# Sheet1.net
KiCad netlist of a schematic drawn in Altium Designer
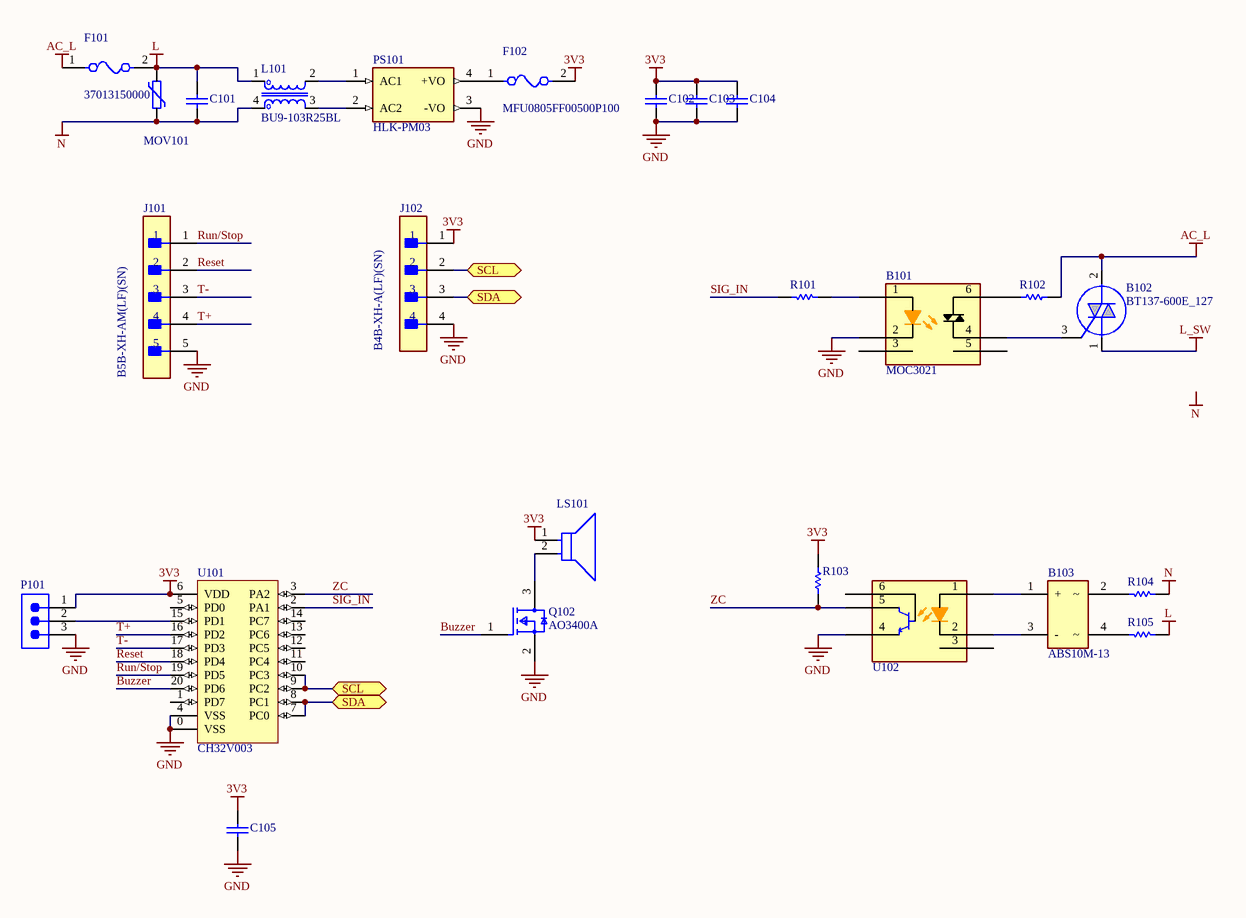
[diagram p0: Sheet1.SchDoc]

(export (version "E")
  (design (tool "Eeschema 10.0.6"))
  (components
    (comp (ref "B101")
      (value "MOC3021")
      (footprint "MOC3021")
      (fields (field (name "MOUSER PART NUMBER") "859-MOC3021"))
      (libsource (lib "Schlib1") (part "MOC3021"))
    )
    (comp (ref "B102")
      (value "BT137-600E_127")
      (footprint "TO254P470X1000X2000-3P")
      (fields
        (field (name "MANUFACTURER_PART_NUMBER") "BT137-600E,127")
        (field (name "MOUSER PART NUMBER") "771-BT137-600E")
      )
      (libsource (lib "Schlib1") (part "BT137-600E_127"))
    )
    (comp (ref "B103")
      (value "ABS10M-13")
      (footprint "SOP400P660X140-4N")
      (description "Bridge Rectifier Single Phase Standard 1 kV Surface Mount 4-SOPA (Type WX)")
      (fields (field (name "MOUSER PART NUMBER") "621-ABS10M-13"))
      (libsource (lib "Schlib1") (part "ABS10M-13"))
    )
    (comp (ref "C101")
      (value "890324023023")
      (footprint "WCAP-FTX2_L13W7H13")
      (fields (field (name "TOLERANCE") "10%"))
      (libsource (lib "Altium Content Vault") (part "Capacitor_Non-Polarized"))
    )
    (comp (ref "C102")
      (value "Capacitor")
      (footprint "CAPC2013X13N")
      (libsource (lib "Schlib1") (part "C0805"))
    )
    (comp (ref "C103")
      (value "Capacitor")
      (footprint "CAPC2013X13N")
      (libsource (lib "Schlib1") (part "C0805"))
    )
    (comp (ref "C104")
      (value "Capacitor")
      (footprint "CAPC2013X13N")
      (libsource (lib "Schlib1") (part "C0805"))
    )
    (comp (ref "C105")
      (value "Capacitor")
      (footprint "CAPC1608X09N")
      (libsource (lib "Schlib1") (part "C0603"))
    )
    (comp (ref "F101")
      (value "37013150000")
      (footprint "FP-370-MFG")
      (description "FUSE BRD MNT 3.15A 250VAC RADIAL")
      (libsource (lib "Altium Content Vault") (part "5bcf9b9f640e542cf0359d10258e979"))
    )
    (comp (ref "F102")
      (value "MFU0805FF00500P100")
      (footprint "FP-MFU0805-MFG")
      (libsource (lib "Altium Content Vault") (part "5bcf9b9f640e542cf0359d10258e979"))
    )
    (comp (ref "J101")
      (value "B5B-XH-AM(LF)(SN)")
      (footprint "FP-B5B-XH-AM_LF_SN-MFG")
      (description "CONN HEADER VERT 5POS 2.5MM")
      (libsource (lib "Altium Content Vault") (part "bf93c07fd2649a848d0ec8585582aab"))
    )
    (comp (ref "J102")
      (value "B4B-XH-A(LF)(SN)")
      (footprint "FP-B4B-XH-A_LF_SN-MFG")
      (description "CONN HEADER VERT 4POS 2.5MM")
      (libsource (lib "Altium Content Vault") (part "299a8cea1bdcbc3624fe62c390fa72c"))
    )
    (comp (ref "L101")
      (value "BU9-103R25BL")
      (footprint "IND_BU9-103R25BL")
      (description "Common mode choke, power line, RoHS")
      (libsource (lib "Schlib1") (part "BU9-103R25BL"))
    )
    (comp (ref "LS101")
      (value "MCKPX-G1203A-K4056")
      (footprint "FP-MCKPX-G1203A-K4056-MFG")
      (description "MAGNETIC BUZZER AND TRANSDUCER - More Details")
      (fields
        (field (name "MANUFACTURER") "Multicomp Pro")
        (field (name "OCTOPART") "https://octopart.com/mckpx-g1203a-k4056-multicomp-12157154")
      )
      (libsource (lib "Altium Content Vault") (part "1973c4b650225fd2ddacaff6b763965"))
    )
    (comp (ref "MOV101") (value "MOV") (footprint "MOV-10D561") (libsource (lib "Schlib1") (part "MOV")))
    (comp (ref "P101")
      (value "61300311121")
      (footprint "61300311121")
      (libsource (lib "Altium Content Vault") (part "Header_Male_1R_03P"))
    )
    (comp (ref "PS101")
      (value "HLK-PM03")
      (footprint "HLK-PM03")
      (fields (field (name "MF") "Hi-link"))
      (libsource (lib "Schlib1") (part "HLK-PM03"))
    )
    (comp (ref "Q102")
      (value "AO3400A")
      (footprint "FP-SOT23-MFG")
      (description "MOSFET N-CH 30V 5.7A SOT23")
      (libsource (lib "Altium Content Vault") (part "0a9ea7c96deaaede766a5b531c28de0"))
    )
    (comp (ref "R101")
      (value "Resistor")
      (footprint "RESC1608X06N")
      (libsource (lib "Schlib1") (part "R0603"))
    )
    (comp (ref "R102")
      (value "Resistor 1/2W")
      (footprint "RESAD1650W60L650D250")
      (description "Resistor")
      (libsource (lib "Schlib1") (part "R_DIP"))
    )
    (comp (ref "R103")
      (value "Resistor")
      (footprint "RESC1608X06N")
      (libsource (lib "Schlib1") (part "R0603"))
    )
    (comp (ref "R104")
      (value "Resistor 1/2W")
      (footprint "RESAD1650W60L650D250")
      (description "30k")
      (libsource (lib "Schlib1") (part "R_DIP"))
    )
    (comp (ref "R105")
      (value "Resistor 1/2W")
      (footprint "RESAD1650W60L650D250")
      (description "30k")
      (libsource (lib "Schlib1") (part "R_DIP"))
    )
    (comp (ref "U101")
      (value "CH32V003")
      (footprint "QFN40P300X300X75_HS-21N")
      (libsource (lib "Schlib1") (part "CH32V003F4U6"))
    )
    (comp (ref "U102")
      (value "Optocoupler, Phototransistor Output, with Base Connection")
      (footprint "MOC3021")
      (libsource (lib "Schlib1") (part "4N25"))
    )
  )
  (nets
    (net (code "1") (name "/Buzzer") (class "Default")
      (node (ref "Q102") (pin "1") (pinfunction "G_1") (pintype "passive"))
      (node (ref "U101") (pin "20") (pinfunction "PD6_20") (pintype "bidirectional"))
    )
    (net (code "2") (name "/Reset") (class "Default")
      (node (ref "J101") (pin "2") (pinfunction "2_2") (pintype "passive"))
      (node (ref "U101") (pin "18") (pinfunction "PD4_18") (pintype "bidirectional"))
    )
    (net (code "3") (name "/Run{slash}Stop") (class "Default")
      (node (ref "J101") (pin "1") (pinfunction "1_1") (pintype "passive"))
      (node (ref "U101") (pin "19") (pinfunction "PD5_19") (pintype "bidirectional"))
    )
    (net (code "4") (name "/SCL") (class "Default")
      (node (ref "J102") (pin "2") (pinfunction "2_2") (pintype "passive"))
      (node (ref "U101") (pin "10") (pinfunction "PC3_10") (pintype "bidirectional"))
      (node (ref "U101") (pin "9") (pinfunction "PC2_9") (pintype "bidirectional"))
    )
    (net (code "5") (name "/SDA") (class "Default")
      (node (ref "J102") (pin "3") (pinfunction "3_3") (pintype "passive"))
      (node (ref "U101") (pin "7") (pinfunction "PC0_7") (pintype "bidirectional"))
      (node (ref "U101") (pin "8") (pinfunction "PC1_8") (pintype "bidirectional"))
    )
    (net (code "6") (name "/SIG_IN") (class "Default")
      (node (ref "R101") (pin "2") (pintype "passive"))
      (node (ref "U101") (pin "2") (pinfunction "PA1_2") (pintype "bidirectional"))
    )
    (net (code "7") (name "/T+") (class "Default")
      (node (ref "J101") (pin "4") (pinfunction "4_4") (pintype "passive"))
      (node (ref "U101") (pin "16") (pinfunction "PD2_16") (pintype "bidirectional"))
    )
    (net (code "8") (name "/T-") (class "Default")
      (node (ref "J101") (pin "3") (pinfunction "3_3") (pintype "passive"))
      (node (ref "U101") (pin "17") (pinfunction "PD3_17") (pintype "bidirectional"))
    )
    (net (code "9") (name "/ZC") (class "Default")
      (node (ref "R103") (pin "1") (pintype "passive"))
      (node (ref "U101") (pin "3") (pinfunction "PA2_3") (pintype "bidirectional"))
      (node (ref "U102") (pin "5") (pinfunction "SUBSTRATE_5") (pintype "passive"))
    )
    (net (code "10") (name "3V3") (class "Default")
      (node (ref "C102") (pin "2") (pintype "passive"))
      (node (ref "C103") (pin "2") (pintype "passive"))
      (node (ref "C104") (pin "2") (pintype "passive"))
      (node (ref "C105") (pin "2") (pintype "passive"))
      (node (ref "F102") (pin "2") (pinfunction "2_2") (pintype "passive"))
      (node (ref "J102") (pin "1") (pinfunction "1_1") (pintype "passive"))
      (node (ref "LS101") (pin "1") (pinfunction "C_1") (pintype "passive"))
      (node (ref "P101") (pin "1") (pinfunction "1_1") (pintype "passive"))
      (node (ref "R103") (pin "2") (pintype "passive"))
      (node (ref "U101") (pin "6") (pinfunction "VDD_6") (pintype "power_in"))
    )
    (net (code "11") (name "AC_L") (class "Default")
      (node (ref "B102") (pin "2") (pinfunction "MT2_2") (pintype "passive"))
      (node (ref "F101") (pin "1") (pinfunction "1_1") (pintype "passive"))
      (node (ref "R102") (pin "2") (pintype "passive"))
    )
    (net (code "12") (name "GND") (class "Default")
      (node (ref "B101") (pin "2") (pinfunction "CATHODE_2") (pintype "passive"))
      (node (ref "C102") (pin "1") (pintype "passive"))
      (node (ref "C103") (pin "1") (pintype "passive"))
      (node (ref "C104") (pin "1") (pintype "passive"))
      (node (ref "C105") (pin "1") (pintype "passive"))
      (node (ref "J101") (pin "5") (pinfunction "5_5") (pintype "passive"))
      (node (ref "J102") (pin "4") (pinfunction "4_4") (pintype "passive"))
      (node (ref "P101") (pin "3") (pinfunction "3_3") (pintype "passive"))
      (node (ref "PS101") (pin "3") (pinfunction "-VO_3") (pintype "output"))
      (node (ref "Q102") (pin "2") (pinfunction "S_2") (pintype "passive"))
      (node (ref "U101") (pin "0") (pinfunction "VSS_0") (pintype "power_in"))
      (node (ref "U101") (pin "4") (pinfunction "VSS_4") (pintype "power_in"))
      (node (ref "U102") (pin "4") (pinfunction "MAIN_TERMINAL_1_4") (pintype "passive"))
    )
    (net (code "13") (name "L") (class "Default")
      (node (ref "C101") (pin "2") (pinfunction "2_2") (pintype "passive"))
      (node (ref "F101") (pin "2") (pinfunction "2_2") (pintype "passive"))
      (node (ref "L101") (pin "1") (pinfunction "1_1") (pintype "passive"))
      (node (ref "MOV101") (pin "2") (pintype "passive"))
      (node (ref "R105") (pin "1") (pintype "passive"))
    )
    (net (code "14") (name "L_SW") (class "Default")
      (node (ref "B102") (pin "1") (pinfunction "MT1_1") (pintype "passive"))
    )
    (net (code "15") (name "N") (class "Default")
      (node (ref "C101") (pin "1") (pinfunction "1_1") (pintype "passive"))
      (node (ref "L101") (pin "4") (pinfunction "4_4") (pintype "passive"))
      (node (ref "MOV101") (pin "1") (pintype "passive"))
      (node (ref "R104") (pin "1") (pintype "passive"))
    )
    (net (code "16") (name "Net-(B101-ANODE)") (class "Default")
      (node (ref "B101") (pin "1") (pinfunction "ANODE_1") (pintype "passive"))
      (node (ref "R101") (pin "1") (pintype "passive"))
    )
    (net (code "17") (name "Net-(B101-MAIN_TERMINAL_1)") (class "Default")
      (node (ref "B101") (pin "4") (pinfunction "MAIN_TERMINAL_1_4") (pintype "passive"))
      (node (ref "B102") (pin "3") (pinfunction "G_3") (pintype "passive"))
    )
    (net (code "18") (name "Net-(B101-MAIN_TERMINAL_2)") (class "Default")
      (node (ref "B101") (pin "6") (pinfunction "MAIN_TERMINAL_2_6") (pintype "passive"))
      (node (ref "R102") (pin "1") (pintype "passive"))
    )
    (net (code "19") (name "Net-(B103-+)") (class "Default")
      (node (ref "B103") (pin "1") (pinfunction "+_1") (pintype "power_in"))
      (node (ref "U102") (pin "1") (pinfunction "ANODE_1") (pintype "passive"))
    )
    (net (code "20") (name "Net-(B103--)") (class "Default")
      (node (ref "B103") (pin "3") (pinfunction "-_3") (pintype "power_in"))
      (node (ref "U102") (pin "2") (pinfunction "CATHODE_2") (pintype "passive"))
    )
    (net (code "21") (name "Net-(B103-~-Pad2)") (class "Default")
      (node (ref "B103") (pin "2") (pinfunction "~_2") (pintype "power_in"))
      (node (ref "R104") (pin "2") (pintype "passive"))
    )
    (net (code "22") (name "Net-(B103-~-Pad4)") (class "Default")
      (node (ref "B103") (pin "4") (pinfunction "~_4") (pintype "power_in"))
      (node (ref "R105") (pin "2") (pintype "passive"))
    )
    (net (code "23") (name "Net-(LS101-A)") (class "Default")
      (node (ref "LS101") (pin "2") (pinfunction "A_2") (pintype "passive"))
      (node (ref "Q102") (pin "3") (pinfunction "D_3") (pintype "passive"))
    )
    (net (code "24") (name "Net-(PS101-+VO)") (class "Default")
      (node (ref "F102") (pin "1") (pinfunction "1_1") (pintype "passive"))
      (node (ref "PS101") (pin "4") (pinfunction "+VO_4") (pintype "output"))
    )
    (net (code "25") (name "Net-(PS101-AC1)") (class "Default")
      (node (ref "L101") (pin "2") (pinfunction "2_2") (pintype "passive"))
      (node (ref "PS101") (pin "1") (pinfunction "AC1_1") (pintype "input"))
    )
    (net (code "26") (name "Net-(PS101-AC2)") (class "Default")
      (node (ref "L101") (pin "3") (pinfunction "3_3") (pintype "passive"))
      (node (ref "PS101") (pin "2") (pinfunction "AC2_2") (pintype "input"))
    )
    (net (code "27") (name "Net-(U101-PD1)") (class "Default")
      (node (ref "P101") (pin "2") (pinfunction "2_2") (pintype "passive"))
      (node (ref "U101") (pin "15") (pinfunction "PD1_15") (pintype "bidirectional"))
    )
    (net (code "28") (name "unconnected-(B101-NC-Pad3)") (class "Default")
      (node (ref "B101") (pin "3") (pinfunction "NC_3") (pintype "passive"))
    )
    (net (code "29") (name "unconnected-(B101-SUBSTRATE-Pad5)") (class "Default")
      (node (ref "B101") (pin "5") (pinfunction "SUBSTRATE_5") (pintype "passive"))
    )
    (net (code "30") (name "unconnected-(U101-PC4-Pad11)") (class "Default")
      (node (ref "U101") (pin "11") (pinfunction "PC4_11") (pintype "bidirectional"))
    )
    (net (code "31") (name "unconnected-(U101-PC5-Pad12)") (class "Default")
      (node (ref "U101") (pin "12") (pinfunction "PC5_12") (pintype "bidirectional"))
    )
    (net (code "32") (name "unconnected-(U101-PC6-Pad13)") (class "Default")
      (node (ref "U101") (pin "13") (pinfunction "PC6_13") (pintype "bidirectional"))
    )
    (net (code "33") (name "unconnected-(U101-PC7-Pad14)") (class "Default")
      (node (ref "U101") (pin "14") (pinfunction "PC7_14") (pintype "bidirectional"))
    )
    (net (code "34") (name "unconnected-(U101-PD0-Pad5)") (class "Default")
      (node (ref "U101") (pin "5") (pinfunction "PD0_5") (pintype "bidirectional"))
    )
    (net (code "35") (name "unconnected-(U101-PD7-Pad1)") (class "Default")
      (node (ref "U101") (pin "1") (pinfunction "PD7_1") (pintype "bidirectional"))
    )
    (net (code "36") (name "unconnected-(U102-MAIN_TERMINAL_2-Pad6)") (class "Default")
      (node (ref "U102") (pin "6") (pinfunction "MAIN_TERMINAL_2_6") (pintype "passive"))
    )
    (net (code "37") (name "unconnected-(U102-NC-Pad3)") (class "Default")
      (node (ref "U102") (pin "3") (pinfunction "NC_3") (pintype "passive"))
    )
  )
)
